# 9_Front_Pannel_USB_Con.net
KiCad netlist of a schematic drawn in Altium Designer
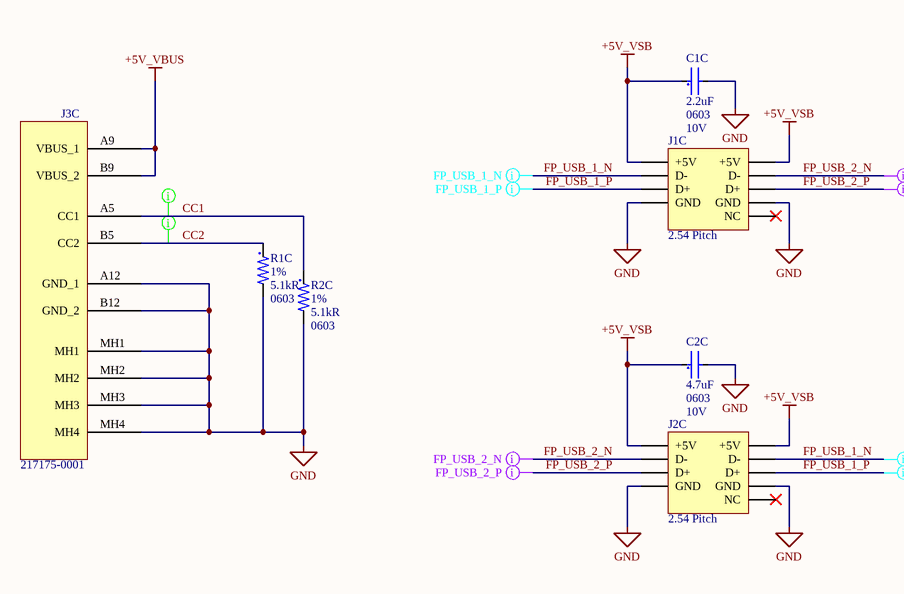
[diagram p0: 9_Front_Pannel_USB_Con.SchDoc]

(export (version "E")
  (design (tool "Eeschema 10.0.6"))
  (components
    (comp (ref "C1C")
      (value "2.2uF")
      (footprint "C0603-IPC_C_No_Silk")
      (description "Multilayer Ceramic Capacitor, 2.2 uF, 10 V, ± 10%, X7R, 0603 [1608 Metric]")
      (fields
        (field (name "MANUFACTURER") "TDK")
        (field (name "MANUFACTURER PART NUMBER") "C1608X7R1A225K080AC")
        (field (name "CASE CODE (IMPERIAL)") "0603")
        (field (name "VOLTAGE RATING") "10V")
      )
      (libsource (lib "Lib_Capacitor_0603") (part "2.2uF_10V"))
    )
    (comp (ref "C2C")
      (value "4.7uF")
      (footprint "C0603-IPC_C_No_Silk")
      (description "Multilayer Ceramic Capacitor, 4.7 uF, 10 V, ± 10%, X5R, 0603 [1608 Metric]")
      (fields
        (field (name "MANUFACTURER") "Samsung")
        (field (name "MANUFACTURER PART NUMBER") "CL10A475KP8NNNC")
        (field (name "CASE CODE (IMPERIAL)") "0603")
        (field (name "VOLTAGE RATING") "10V")
      )
      (libsource (lib "Lib_Capacitor_0603") (part "4.7uF_10V"))
    )
    (comp (ref "J1C")
      (value "2.54 Pitch")
      (footprint "USB_Front_Pannel_2x05_P2.54mm_Horizontal_Right")
      (libsource (lib "Lib_Connector_PinHeader_2.54mm") (part "USB_Front_Pannel_2x05_P2.54mm"))
    )
    (comp (ref "J2C")
      (value "2.54 Pitch")
      (footprint "USB_Front_Pannel_2x05_P2.54mm_Horizontal_Left")
      (libsource (lib "Lib_Connector_PinHeader_2.54mm") (part "USB_Front_Pannel_2x05_P2.54mm"))
    )
    (comp (ref "J3C")
      (value "217175-0001")
      (footprint "USB-Type-C-6-Pin-SMT")
      (description "Connector USB Type C Female 6Positions 0.5mm Right Angle SMT Embossed T/R - Tape and Reel")
      (fields (field (name "MOUSER PART NUMBER") "538-217175-0001"))
      (libsource (lib "Lib_Connector") (part "USB-Type-C-6-Pin-SMT"))
    )
    (comp (ref "R1C")
      (value "5.1kR")
      (footprint "R0603-MFG")
      (description "SMD Chip Resistor, 5.1 kOhm, ± 1%, 100 mW, 0603 [1608 Metric], Thick Film, General Purpose")
      (fields
        (field (name "MANUFACTURER") "Vishay")
        (field (name "MANUFACTURER PART NUMBER") "CRCW06035K10FKEA")
        (field (name "TOLERANCE") "1%")
        (field (name "CASE/PACKAGE") "0603")
      )
      (libsource (lib "Lib_Register_0603") (part "5.1K"))
    )
    (comp (ref "R2C")
      (value "5.1kR")
      (footprint "R0603-MFG")
      (description "SMD Chip Resistor, 5.1 kOhm, ± 1%, 100 mW, 0603 [1608 Metric], Thick Film, General Purpose")
      (fields
        (field (name "MANUFACTURER") "Vishay")
        (field (name "MANUFACTURER PART NUMBER") "CRCW06035K10FKEA")
        (field (name "TOLERANCE") "1%")
        (field (name "CASE/PACKAGE") "0603")
      )
      (libsource (lib "Lib_Register_0603") (part "5.1K"))
    )
  )
  (nets
    (net (code "1") (name "+5V_VBUS") (class "Default")
      (node (ref "J3C") (pin "A9") (pinfunction "VBUS_1_A9") (pintype "passive"))
      (node (ref "J3C") (pin "B9") (pinfunction "VBUS_2_B9") (pintype "passive"))
    )
    (net (code "2") (name "+5V_VSB") (class "Default")
      (node (ref "C1C") (pin "1") (pinfunction "1_1") (pintype "passive"))
      (node (ref "C2C") (pin "1") (pinfunction "1_1") (pintype "passive"))
      (node (ref "J1C") (pin "1") (pinfunction "+5V_1") (pintype "passive"))
      (node (ref "J1C") (pin "2") (pinfunction "+5V_2") (pintype "passive"))
      (node (ref "J2C") (pin "1") (pinfunction "+5V_1") (pintype "passive"))
      (node (ref "J2C") (pin "2") (pinfunction "+5V_2") (pintype "passive"))
    )
    (net (code "3") (name "/CC1") (class "Default")
      (node (ref "J3C") (pin "A5") (pinfunction "CC1_A5") (pintype "passive"))
      (node (ref "R2C") (pin "1") (pinfunction "1_1") (pintype "passive"))
    )
    (net (code "4") (name "/CC2") (class "Default")
      (node (ref "J3C") (pin "B5") (pinfunction "CC2_B5") (pintype "passive"))
      (node (ref "R1C") (pin "1") (pinfunction "1_1") (pintype "passive"))
    )
    (net (code "5") (name "/FP_USB_1_N") (class "Default")
      (node (ref "J1C") (pin "3") (pinfunction "D-_3") (pintype "passive"))
      (node (ref "J2C") (pin "4") (pinfunction "D-_4") (pintype "passive"))
    )
    (net (code "6") (name "/FP_USB_1_P") (class "Default")
      (node (ref "J1C") (pin "5") (pinfunction "D+_5") (pintype "passive"))
      (node (ref "J2C") (pin "6") (pinfunction "D+_6") (pintype "passive"))
    )
    (net (code "7") (name "/FP_USB_2_N") (class "Default")
      (node (ref "J1C") (pin "4") (pinfunction "D-_4") (pintype "passive"))
      (node (ref "J2C") (pin "3") (pinfunction "D-_3") (pintype "passive"))
    )
    (net (code "8") (name "/FP_USB_2_P") (class "Default")
      (node (ref "J1C") (pin "6") (pinfunction "D+_6") (pintype "passive"))
      (node (ref "J2C") (pin "5") (pinfunction "D+_5") (pintype "passive"))
    )
    (net (code "9") (name "GND") (class "Default")
      (node (ref "C1C") (pin "2") (pinfunction "2_2") (pintype "passive"))
      (node (ref "C2C") (pin "2") (pinfunction "2_2") (pintype "passive"))
      (node (ref "J1C") (pin "7") (pinfunction "GND_7") (pintype "passive"))
      (node (ref "J1C") (pin "8") (pinfunction "GND_8") (pintype "passive"))
      (node (ref "J2C") (pin "7") (pinfunction "GND_7") (pintype "passive"))
      (node (ref "J2C") (pin "8") (pinfunction "GND_8") (pintype "passive"))
      (node (ref "J3C") (pin "A12") (pinfunction "GND_1_A12") (pintype "passive"))
      (node (ref "J3C") (pin "B12") (pinfunction "GND_2_B12") (pintype "passive"))
      (node (ref "J3C") (pin "MH1") (pinfunction "MH1_MH1") (pintype "passive"))
      (node (ref "J3C") (pin "MH2") (pinfunction "MH2_MH2") (pintype "passive"))
      (node (ref "J3C") (pin "MH3") (pinfunction "MH3_MH3") (pintype "passive"))
      (node (ref "J3C") (pin "MH4") (pinfunction "MH4_MH4") (pintype "passive"))
      (node (ref "R1C") (pin "2") (pinfunction "2_2") (pintype "passive"))
      (node (ref "R2C") (pin "2") (pinfunction "2_2") (pintype "passive"))
    )
    (net (code "10") (name "unconnected-(J1C-NC-Pad10)") (class "Default")
      (node (ref "J1C") (pin "10") (pinfunction "NC_10") (pintype "passive+no_connect"))
    )
    (net (code "11") (name "unconnected-(J2C-NC-Pad10)") (class "Default")
      (node (ref "J2C") (pin "10") (pinfunction "NC_10") (pintype "passive+no_connect"))
    )
  )
)
